# TJ_Gen1_Prototype.net
KiCad netlist of a schematic drawn in EAGLE
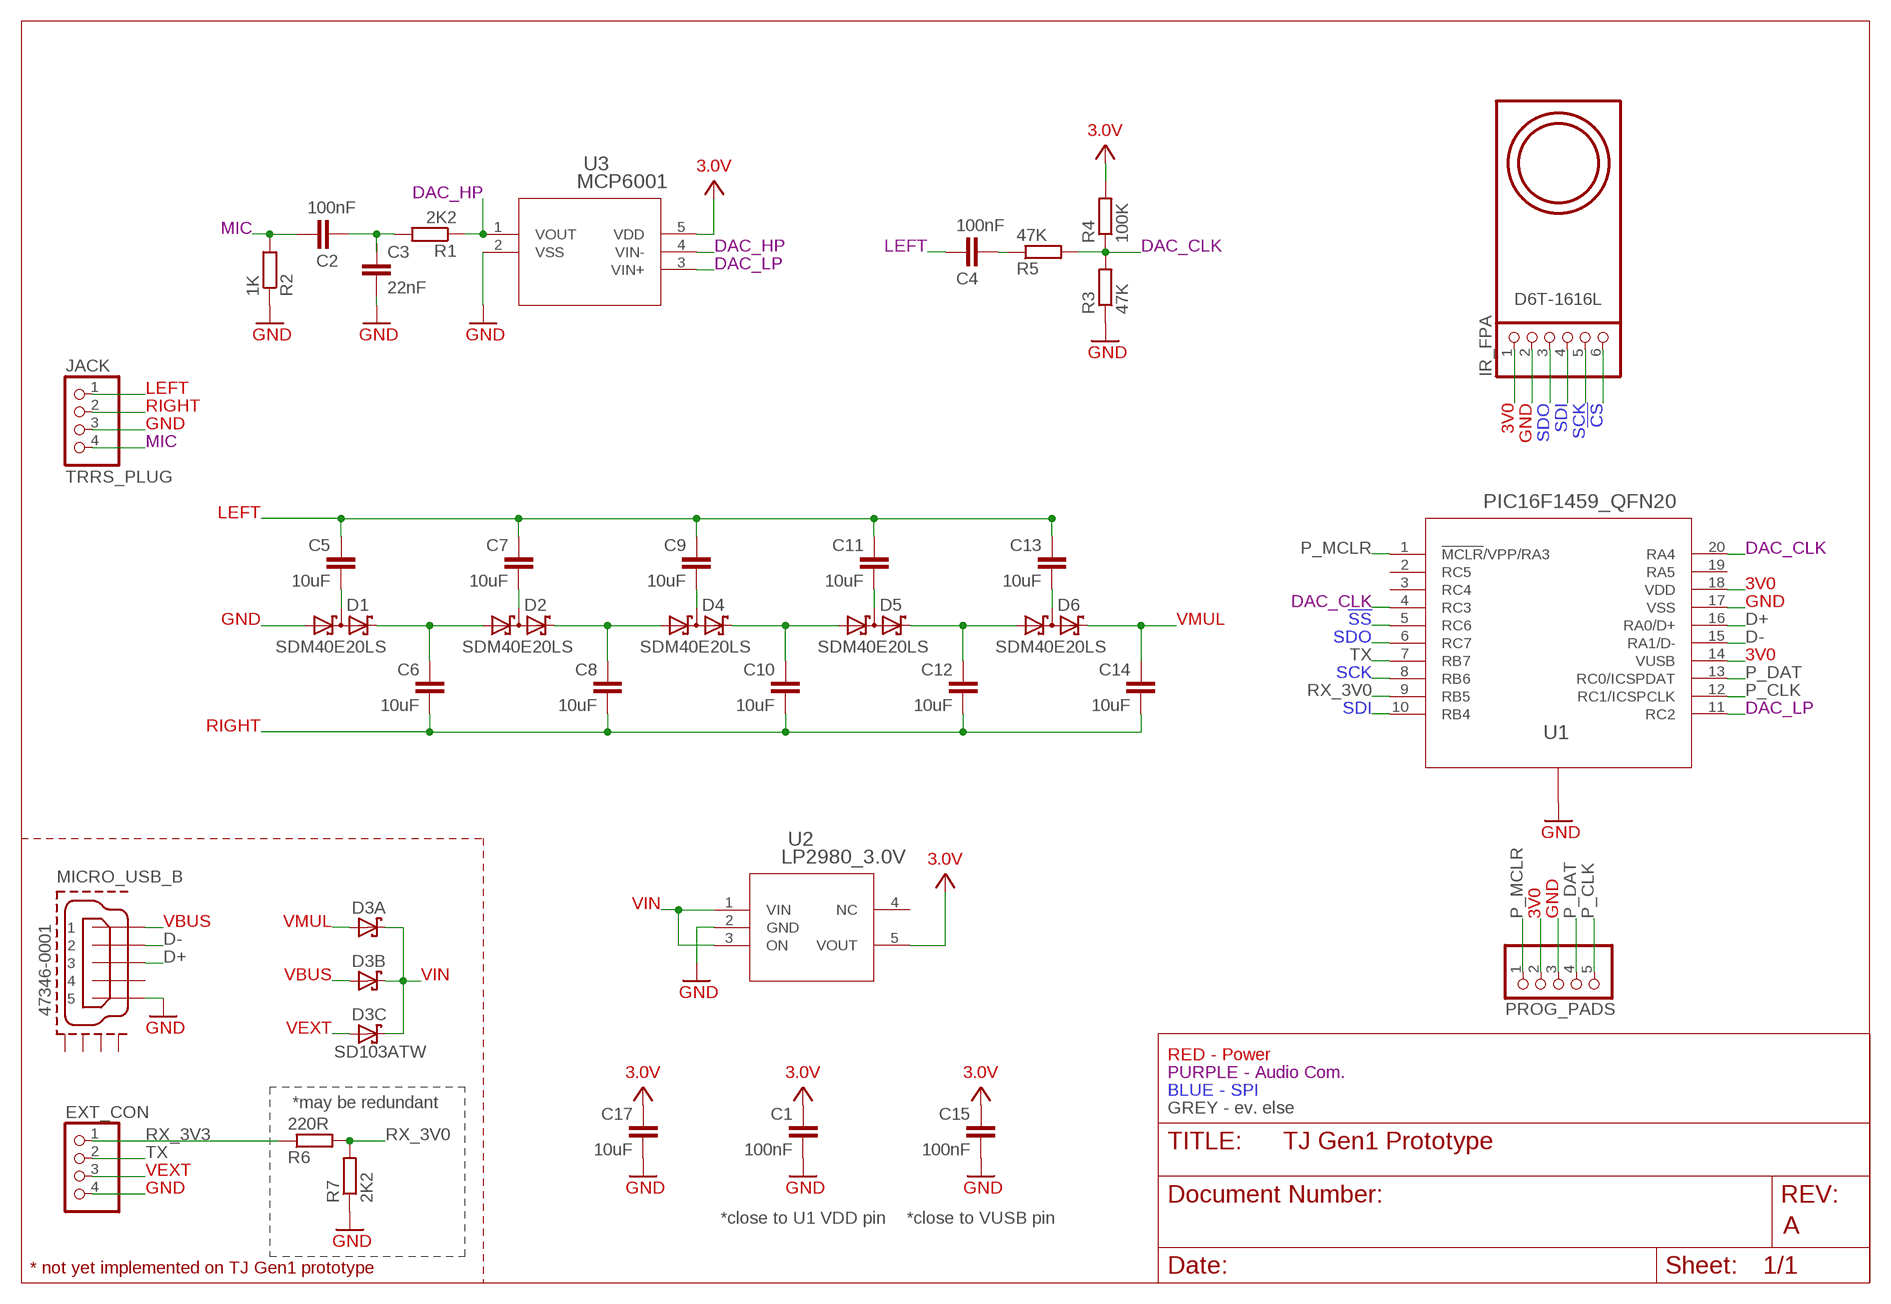
[diagram p0: schematic, sheet 1]

(export (version "E")
  (design (tool "Eeschema 10.0.6"))
  (components
    (comp (ref "C1")
      (value "100nF")
      (footprint "eagle-import:C0603")
      (libsource (lib "eagle-import") (part "C-EUC0603"))
    )
    (comp (ref "C2")
      (value "100nF")
      (footprint "eagle-import:C0603")
      (libsource (lib "eagle-import") (part "C-EUC0603"))
    )
    (comp (ref "C3")
      (value "22nF")
      (footprint "eagle-import:C0603")
      (libsource (lib "eagle-import") (part "C-EUC0603"))
    )
    (comp (ref "C4")
      (value "100nF")
      (footprint "eagle-import:C0603")
      (libsource (lib "eagle-import") (part "C-EUC0603"))
    )
    (comp (ref "C5")
      (value "10uF")
      (footprint "eagle-import:C0603")
      (libsource (lib "eagle-import") (part "C-EUC0603"))
    )
    (comp (ref "C6")
      (value "10uF")
      (footprint "eagle-import:C0603")
      (libsource (lib "eagle-import") (part "C-EUC0603"))
    )
    (comp (ref "C7")
      (value "10uF")
      (footprint "eagle-import:C0603")
      (libsource (lib "eagle-import") (part "C-EUC0603"))
    )
    (comp (ref "C8")
      (value "10uF")
      (footprint "eagle-import:C0603")
      (libsource (lib "eagle-import") (part "C-EUC0603"))
    )
    (comp (ref "C9")
      (value "10uF")
      (footprint "eagle-import:C0603")
      (libsource (lib "eagle-import") (part "C-EUC0603"))
    )
    (comp (ref "C10")
      (value "10uF")
      (footprint "eagle-import:C0603")
      (libsource (lib "eagle-import") (part "C-EUC0603"))
    )
    (comp (ref "C11")
      (value "10uF")
      (footprint "eagle-import:C0603")
      (libsource (lib "eagle-import") (part "C-EUC0603"))
    )
    (comp (ref "C12")
      (value "10uF")
      (footprint "eagle-import:C0603")
      (libsource (lib "eagle-import") (part "C-EUC0603"))
    )
    (comp (ref "C13")
      (value "10uF")
      (footprint "eagle-import:C0603")
      (libsource (lib "eagle-import") (part "C-EUC0603"))
    )
    (comp (ref "C14")
      (value "10uF")
      (footprint "eagle-import:C0603")
      (libsource (lib "eagle-import") (part "C-EUC0603"))
    )
    (comp (ref "C15")
      (value "100nF")
      (footprint "eagle-import:C0603")
      (libsource (lib "eagle-import") (part "C-EUC0603"))
    )
    (comp (ref "C17")
      (value "10uF")
      (footprint "eagle-import:C0603")
      (libsource (lib "eagle-import") (part "C-EUC0603"))
    )
    (comp (ref "D1")
      (value "SDM40E20LS")
      (footprint "eagle-import:SOT23")
      (libsource (lib "eagle-import") (part "BAS40-04"))
    )
    (comp (ref "D2")
      (value "SDM40E20LS")
      (footprint "eagle-import:SOT23")
      (libsource (lib "eagle-import") (part "BAS40-04"))
    )
    (comp (ref "D3")
      (value "SD103ATW")
      (footprint "eagle-import:SOT666")
      (libsource (lib "eagle-import") (part "BAS70VV"))
    )
    (comp (ref "D4")
      (value "SDM40E20LS")
      (footprint "eagle-import:SOT23")
      (libsource (lib "eagle-import") (part "BAS40-04"))
    )
    (comp (ref "D5")
      (value "SDM40E20LS")
      (footprint "eagle-import:SOT23")
      (libsource (lib "eagle-import") (part "BAS40-04"))
    )
    (comp (ref "D6")
      (value "SDM40E20LS")
      (footprint "eagle-import:SOT23")
      (libsource (lib "eagle-import") (part "BAS40-04"))
    )
    (comp (ref "EXT_CON")
      (value "PINHD-1X4")
      (footprint "eagle-import:1X04")
      (libsource (lib "eagle-import") (part "PINHD-1X4"))
    )
    (comp (ref "IR_FPA")
      (value "D6T-1616L")
      (footprint "eagle-import:1X06")
      (libsource (lib "eagle-import") (part "PINHD-1X6"))
    )
    (comp (ref "JACK")
      (value "TRRS_PLUG")
      (footprint "eagle-import:1X04")
      (libsource (lib "eagle-import") (part "PINHD-1X4"))
    )
    (comp (ref "MICRO_USB_B")
      (value "47346-0001")
      (footprint "eagle-import:MOLEX-47364-0001")
      (libsource (lib "eagle-import") (part "MOLEX-47346-0001"))
    )
    (comp (ref "PROG_PADS")
      (value "PINHD-1X5")
      (footprint "eagle-import:1X05")
      (libsource (lib "eagle-import") (part "PINHD-1X5"))
    )
    (comp (ref "R1")
      (value "2K2")
      (footprint "eagle-import:R0603")
      (libsource (lib "eagle-import") (part "R-EU_R0603"))
    )
    (comp (ref "R2")
      (value "1K")
      (footprint "eagle-import:R0603")
      (libsource (lib "eagle-import") (part "R-EU_R0603"))
    )
    (comp (ref "R3")
      (value "47K")
      (footprint "eagle-import:R0603")
      (libsource (lib "eagle-import") (part "R-EU_R0603"))
    )
    (comp (ref "R4")
      (value "100K")
      (footprint "eagle-import:R0603")
      (libsource (lib "eagle-import") (part "R-EU_R0603"))
    )
    (comp (ref "R5")
      (value "47K")
      (footprint "eagle-import:R0603")
      (libsource (lib "eagle-import") (part "R-EU_R0603"))
    )
    (comp (ref "R6")
      (value "220R")
      (footprint "eagle-import:R0603")
      (libsource (lib "eagle-import") (part "R-EU_R0603"))
    )
    (comp (ref "R7")
      (value "2K2")
      (footprint "eagle-import:R0603")
      (libsource (lib "eagle-import") (part "R-EU_R0603"))
    )
    (comp (ref "U1")
      (value "PIC16F1459_QFN20")
      (footprint "eagle-import:QFN20_4X4MC")
      (libsource (lib "eagle-import") (part "PIC16F1459-X_ML"))
    )
    (comp (ref "U2")
      (value "LP2980_3.0V")
      (footprint "eagle-import:MF05A")
      (fields (field (name "PARTNUMBER") "LP2980AIM5-25"))
      (libsource (lib "eagle-import") (part "LP2980_DBV_5"))
    )
    (comp (ref "U3")
      (value "MCP6001")
      (footprint "eagle-import:SC70-5_MC")
      (libsource (lib "eagle-import") (part "MCP6001-X/LT"))
    )
  )
  (nets
    (net (code "1") (name "/3V0") (class "Default")
      (node (ref "IR_FPA") (pin "1") (pinfunction "1_1") (pintype "passive"))
      (node (ref "PROG_PADS") (pin "2") (pinfunction "2_2") (pintype "passive"))
      (node (ref "U1") (pin "14") (pinfunction "VUSB_14") (pintype "bidirectional"))
      (node (ref "U1") (pin "18") (pinfunction "VDD_18") (pintype "power_in"))
    )
    (net (code "2") (name "/D+") (class "Default")
      (node (ref "MICRO_USB_B") (pin "3") (pinfunction "3_3") (pintype "input"))
      (node (ref "U1") (pin "16") (pinfunction "RA0/D+_16") (pintype "bidirectional"))
    )
    (net (code "3") (name "/D-") (class "Default")
      (node (ref "MICRO_USB_B") (pin "2") (pinfunction "2_2") (pintype "input"))
      (node (ref "U1") (pin "15") (pinfunction "RA1/D-_15") (pintype "bidirectional"))
    )
    (net (code "4") (name "/DAC_CLK") (class "Default")
      (node (ref "R3") (pin "2") (pinfunction "2_2") (pintype "passive"))
      (node (ref "R4") (pin "1") (pinfunction "1_1") (pintype "passive"))
      (node (ref "R5") (pin "2") (pinfunction "2_2") (pintype "passive"))
      (node (ref "U1") (pin "20") (pinfunction "RA4_20") (pintype "bidirectional"))
      (node (ref "U1") (pin "4") (pinfunction "RC3_4") (pintype "bidirectional"))
    )
    (net (code "5") (name "/DAC_HP") (class "Default")
      (node (ref "R1") (pin "1") (pinfunction "1_1") (pintype "passive"))
      (node (ref "U3") (pin "1") (pinfunction "VOUT_1") (pintype "passive"))
      (node (ref "U3") (pin "4") (pinfunction "VIN-_4") (pintype "passive"))
    )
    (net (code "6") (name "/DAC_LP") (class "Default")
      (node (ref "U1") (pin "11") (pinfunction "RC2_11") (pintype "bidirectional"))
      (node (ref "U3") (pin "3") (pinfunction "VIN+_3") (pintype "passive"))
    )
    (net (code "7") (name "/LEFT") (class "Default")
      (node (ref "C11") (pin "1") (pinfunction "1_1") (pintype "passive"))
      (node (ref "C13") (pin "1") (pinfunction "1_1") (pintype "passive"))
      (node (ref "C4") (pin "1") (pinfunction "1_1") (pintype "passive"))
      (node (ref "C5") (pin "1") (pinfunction "1_1") (pintype "passive"))
      (node (ref "C7") (pin "1") (pinfunction "1_1") (pintype "passive"))
      (node (ref "C9") (pin "1") (pinfunction "1_1") (pintype "passive"))
      (node (ref "JACK") (pin "1") (pinfunction "1_1") (pintype "passive"))
    )
    (net (code "8") (name "/MIC") (class "Default")
      (node (ref "C2") (pin "1") (pinfunction "1_1") (pintype "passive"))
      (node (ref "JACK") (pin "4") (pinfunction "4_4") (pintype "passive"))
      (node (ref "R2") (pin "2") (pinfunction "2_2") (pintype "passive"))
    )
    (net (code "9") (name "/P_CLK") (class "Default")
      (node (ref "PROG_PADS") (pin "5") (pinfunction "5_5") (pintype "passive"))
      (node (ref "U1") (pin "12") (pinfunction "RC1/ICSPCLK_12") (pintype "bidirectional"))
    )
    (net (code "10") (name "/P_DAT") (class "Default")
      (node (ref "PROG_PADS") (pin "4") (pinfunction "4_4") (pintype "passive"))
      (node (ref "U1") (pin "13") (pinfunction "RC0/ICSPDAT_13") (pintype "bidirectional"))
    )
    (net (code "11") (name "/P_MCLR") (class "Default")
      (node (ref "PROG_PADS") (pin "1") (pinfunction "1_1") (pintype "passive"))
      (node (ref "U1") (pin "1") (pinfunction "~{MCLR}/VPP/RA3_1") (pintype "bidirectional"))
    )
    (net (code "12") (name "/RIGHT") (class "Default")
      (node (ref "C10") (pin "2") (pinfunction "2_2") (pintype "passive"))
      (node (ref "C12") (pin "2") (pinfunction "2_2") (pintype "passive"))
      (node (ref "C14") (pin "2") (pinfunction "2_2") (pintype "passive"))
      (node (ref "C6") (pin "2") (pinfunction "2_2") (pintype "passive"))
      (node (ref "C8") (pin "2") (pinfunction "2_2") (pintype "passive"))
      (node (ref "JACK") (pin "2") (pinfunction "2_2") (pintype "passive"))
    )
    (net (code "13") (name "/RX_3V0") (class "Default")
      (node (ref "R6") (pin "2") (pinfunction "2_2") (pintype "passive"))
      (node (ref "R7") (pin "2") (pinfunction "2_2") (pintype "passive"))
      (node (ref "U1") (pin "9") (pinfunction "RB5_9") (pintype "bidirectional"))
    )
    (net (code "14") (name "/RX_3V3") (class "Default")
      (node (ref "EXT_CON") (pin "1") (pinfunction "1_1") (pintype "passive"))
      (node (ref "R6") (pin "1") (pinfunction "1_1") (pintype "passive"))
    )
    (net (code "15") (name "/SCK") (class "Default")
      (node (ref "IR_FPA") (pin "5") (pinfunction "5_5") (pintype "passive"))
      (node (ref "U1") (pin "8") (pinfunction "RB6_8") (pintype "bidirectional"))
    )
    (net (code "16") (name "/SDI") (class "Default")
      (node (ref "IR_FPA") (pin "4") (pinfunction "4_4") (pintype "passive"))
      (node (ref "U1") (pin "10") (pinfunction "RB4_10") (pintype "bidirectional"))
    )
    (net (code "17") (name "/SDO") (class "Default")
      (node (ref "IR_FPA") (pin "3") (pinfunction "3_3") (pintype "passive"))
      (node (ref "U1") (pin "6") (pinfunction "RC7_6") (pintype "bidirectional"))
    )
    (net (code "18") (name "/TX") (class "Default")
      (node (ref "EXT_CON") (pin "2") (pinfunction "2_2") (pintype "passive"))
      (node (ref "U1") (pin "7") (pinfunction "RB7_7") (pintype "bidirectional"))
    )
    (net (code "19") (name "/VBUS") (class "Default")
      (node (ref "D3") (pin "2") (pinfunction "A_2") (pintype "passive"))
      (node (ref "MICRO_USB_B") (pin "1") (pinfunction "1_1") (pintype "input"))
    )
    (net (code "20") (name "/VEXT") (class "Default")
      (node (ref "D3") (pin "3") (pinfunction "A_3") (pintype "passive"))
      (node (ref "EXT_CON") (pin "3") (pinfunction "3_3") (pintype "passive"))
    )
    (net (code "21") (name "/VIN") (class "Default")
      (node (ref "D3") (pin "4") (pinfunction "C_4") (pintype "passive"))
      (node (ref "D3") (pin "5") (pinfunction "C_5") (pintype "passive"))
      (node (ref "D3") (pin "6") (pinfunction "C_6") (pintype "passive"))
      (node (ref "U2") (pin "1") (pinfunction "VIN_1") (pintype "input"))
      (node (ref "U2") (pin "3") (pinfunction "ON_3") (pintype "passive"))
    )
    (net (code "22") (name "/VMUL") (class "Default")
      (node (ref "C14") (pin "1") (pinfunction "1_1") (pintype "passive"))
      (node (ref "D3") (pin "1") (pinfunction "A_1") (pintype "passive"))
      (node (ref "D6") (pin "2") (pinfunction "C2_2") (pintype "passive"))
    )
    (net (code "23") (name "/~{CS}") (class "Default")
      (node (ref "IR_FPA") (pin "6") (pinfunction "6_6") (pintype "passive"))
    )
    (net (code "24") (name "/~{SS}") (class "Default")
      (node (ref "U1") (pin "5") (pinfunction "RC6_5") (pintype "bidirectional"))
    )
    (net (code "25") (name "3.0V") (class "Default")
      (node (ref "C1") (pin "1") (pinfunction "1_1") (pintype "passive"))
      (node (ref "C15") (pin "1") (pinfunction "1_1") (pintype "passive"))
      (node (ref "C17") (pin "1") (pinfunction "1_1") (pintype "passive"))
      (node (ref "R4") (pin "2") (pinfunction "2_2") (pintype "passive"))
      (node (ref "U2") (pin "5") (pinfunction "VOUT_5") (pintype "output"))
      (node (ref "U3") (pin "5") (pinfunction "VDD_5") (pintype "passive"))
    )
    (net (code "26") (name "GND") (class "Default")
      (node (ref "C1") (pin "2") (pinfunction "2_2") (pintype "passive"))
      (node (ref "C15") (pin "2") (pinfunction "2_2") (pintype "passive"))
      (node (ref "C17") (pin "2") (pinfunction "2_2") (pintype "passive"))
      (node (ref "C3") (pin "2") (pinfunction "2_2") (pintype "passive"))
      (node (ref "D1") (pin "1") (pinfunction "A1_1") (pintype "passive"))
      (node (ref "EXT_CON") (pin "4") (pinfunction "4_4") (pintype "passive"))
      (node (ref "IR_FPA") (pin "2") (pinfunction "2_2") (pintype "passive"))
      (node (ref "JACK") (pin "3") (pinfunction "3_3") (pintype "passive"))
      (node (ref "MICRO_USB_B") (pin "5") (pinfunction "5_5") (pintype "input"))
      (node (ref "PROG_PADS") (pin "3") (pinfunction "3_3") (pintype "passive"))
      (node (ref "R2") (pin "1") (pinfunction "1_1") (pintype "passive"))
      (node (ref "R3") (pin "1") (pinfunction "1_1") (pintype "passive"))
      (node (ref "R7") (pin "1") (pinfunction "1_1") (pintype "passive"))
      (node (ref "U1") (pin "17") (pinfunction "VSS_17") (pintype "power_in"))
      (node (ref "U1") (pin "21") (pinfunction "EP_21") (pintype "passive"))
      (node (ref "U2") (pin "2") (pinfunction "GND_2") (pintype "passive"))
      (node (ref "U3") (pin "2") (pinfunction "VSS_2") (pintype "passive"))
    )
    (net (code "27") (name "Net-(C2-Pad2)") (class "Default")
      (node (ref "C2") (pin "2") (pinfunction "2_2") (pintype "passive"))
      (node (ref "C3") (pin "1") (pinfunction "1_1") (pintype "passive"))
      (node (ref "R1") (pin "2") (pinfunction "2_2") (pintype "passive"))
    )
    (net (code "28") (name "Net-(C4-Pad2)") (class "Default")
      (node (ref "C4") (pin "2") (pinfunction "2_2") (pintype "passive"))
      (node (ref "R5") (pin "1") (pinfunction "1_1") (pintype "passive"))
    )
    (net (code "29") (name "Net-(D1-C1A2)") (class "Default")
      (node (ref "C5") (pin "2") (pinfunction "2_2") (pintype "passive"))
      (node (ref "D1") (pin "3") (pinfunction "C1A2_3") (pintype "passive"))
    )
    (net (code "30") (name "Net-(D1-C2)") (class "Default")
      (node (ref "C6") (pin "1") (pinfunction "1_1") (pintype "passive"))
      (node (ref "D1") (pin "2") (pinfunction "C2_2") (pintype "passive"))
      (node (ref "D2") (pin "1") (pinfunction "A1_1") (pintype "passive"))
    )
    (net (code "31") (name "Net-(D2-C1A2)") (class "Default")
      (node (ref "C7") (pin "2") (pinfunction "2_2") (pintype "passive"))
      (node (ref "D2") (pin "3") (pinfunction "C1A2_3") (pintype "passive"))
    )
    (net (code "32") (name "Net-(D2-C2)") (class "Default")
      (node (ref "C8") (pin "1") (pinfunction "1_1") (pintype "passive"))
      (node (ref "D2") (pin "2") (pinfunction "C2_2") (pintype "passive"))
      (node (ref "D4") (pin "1") (pinfunction "A1_1") (pintype "passive"))
    )
    (net (code "33") (name "Net-(D4-C1A2)") (class "Default")
      (node (ref "C9") (pin "2") (pinfunction "2_2") (pintype "passive"))
      (node (ref "D4") (pin "3") (pinfunction "C1A2_3") (pintype "passive"))
    )
    (net (code "34") (name "Net-(D4-C2)") (class "Default")
      (node (ref "C10") (pin "1") (pinfunction "1_1") (pintype "passive"))
      (node (ref "D4") (pin "2") (pinfunction "C2_2") (pintype "passive"))
      (node (ref "D5") (pin "1") (pinfunction "A1_1") (pintype "passive"))
    )
    (net (code "35") (name "Net-(D5-C1A2)") (class "Default")
      (node (ref "C11") (pin "2") (pinfunction "2_2") (pintype "passive"))
      (node (ref "D5") (pin "3") (pinfunction "C1A2_3") (pintype "passive"))
    )
    (net (code "36") (name "Net-(D5-C2)") (class "Default")
      (node (ref "C12") (pin "1") (pinfunction "1_1") (pintype "passive"))
      (node (ref "D5") (pin "2") (pinfunction "C2_2") (pintype "passive"))
      (node (ref "D6") (pin "1") (pinfunction "A1_1") (pintype "passive"))
    )
    (net (code "37") (name "Net-(D6-C1A2)") (class "Default")
      (node (ref "C13") (pin "2") (pinfunction "2_2") (pintype "passive"))
      (node (ref "D6") (pin "3") (pinfunction "C1A2_3") (pintype "passive"))
    )
    (net (code "38") (name "unconnected-(MICRO_USB_B-Pad4)") (class "Default")
      (node (ref "MICRO_USB_B") (pin "4") (pinfunction "4_4") (pintype "input"))
    )
    (net (code "39") (name "unconnected-(MICRO_USB_B-PadGND1)") (class "Default")
      (node (ref "MICRO_USB_B") (pin "GND1") (pinfunction "GND1_GND1") (pintype "bidirectional"))
    )
    (net (code "40") (name "unconnected-(MICRO_USB_B-PadGND2)") (class "Default")
      (node (ref "MICRO_USB_B") (pin "GND2") (pinfunction "GND2_GND2") (pintype "bidirectional"))
    )
    (net (code "41") (name "unconnected-(MICRO_USB_B-PadGND3)") (class "Default")
      (node (ref "MICRO_USB_B") (pin "GND3") (pinfunction "GND3_GND3") (pintype "bidirectional"))
    )
    (net (code "42") (name "unconnected-(MICRO_USB_B-PadGND4)") (class "Default")
      (node (ref "MICRO_USB_B") (pin "GND4") (pinfunction "GND4_GND4") (pintype "bidirectional"))
    )
    (net (code "43") (name "unconnected-(U1-RA5-Pad19)") (class "Default")
      (node (ref "U1") (pin "19") (pinfunction "RA5_19") (pintype "bidirectional"))
    )
    (net (code "44") (name "unconnected-(U1-RC4-Pad3)") (class "Default")
      (node (ref "U1") (pin "3") (pinfunction "RC4_3") (pintype "bidirectional"))
    )
    (net (code "45") (name "unconnected-(U1-RC5-Pad2)") (class "Default")
      (node (ref "U1") (pin "2") (pinfunction "RC5_2") (pintype "bidirectional"))
    )
    (net (code "46") (name "unconnected-(U2-NC-Pad4)") (class "Default")
      (node (ref "U2") (pin "4") (pinfunction "NC_4") (pintype "passive"))
    )
  )
)
